# Audio_output_Codec.net
KiCad netlist of a schematic drawn in Altium Designer
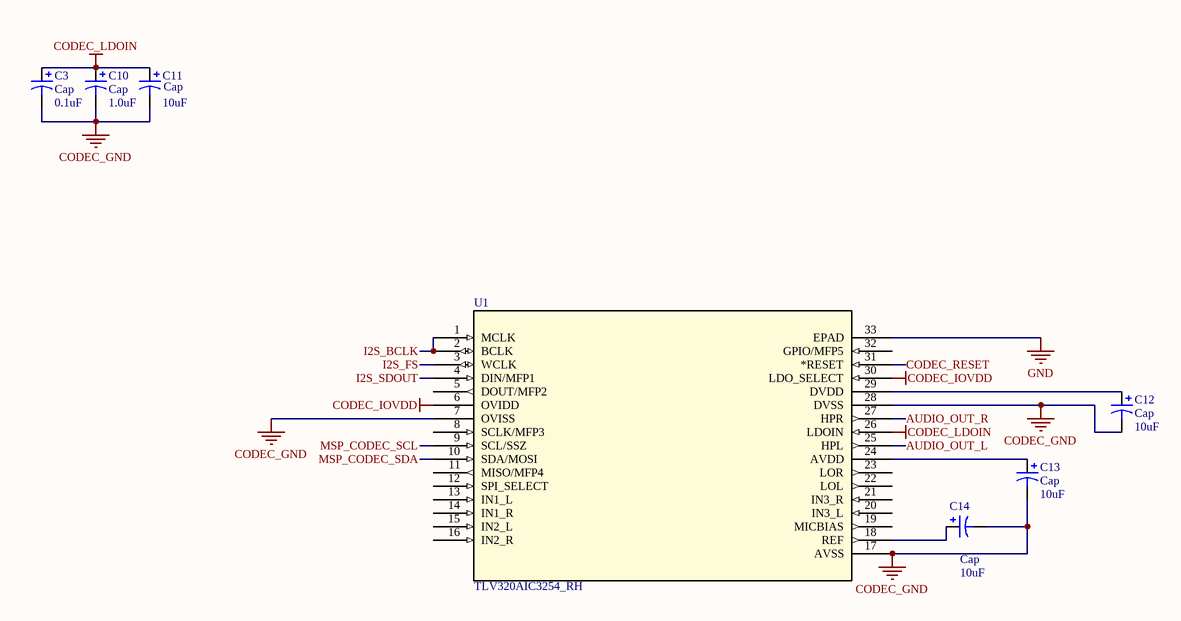
[diagram p0: Audio output Codec.SchDoc]

(export (version "E")
  (design (tool "Eeschema 10.0.6"))
  (components
    (comp (ref "C3")
      (value "Cap")
      (footprint "C0805")
      (description "Polarized Capacitor (Surface Mount)")
      (fields (field (name "ALTIUM_VALUE") "0.1uF") (field (name "PUBLISHER") "Altium Limited"))
      (libsource (lib "Miscellaneous Devices") (part "Cap Pol3"))
    )
    (comp (ref "C10")
      (value "Cap")
      (footprint "C0805")
      (description "Polarized Capacitor (Surface Mount)")
      (fields (field (name "ALTIUM_VALUE") "1.0uF") (field (name "PUBLISHER") "Altium Limited"))
      (libsource (lib "Miscellaneous Devices") (part "Cap Pol3"))
    )
    (comp (ref "C11")
      (value "Cap")
      (footprint "C0805")
      (description "Polarized Capacitor (Surface Mount)")
      (fields (field (name "ALTIUM_VALUE") "10uF") (field (name "PUBLISHER") "Altium Limited"))
      (libsource (lib "Miscellaneous Devices") (part "Cap Pol3"))
    )
    (comp (ref "C12")
      (value "Cap")
      (footprint "C0805")
      (description "Polarized Capacitor (Surface Mount)")
      (fields (field (name "ALTIUM_VALUE") "10uF") (field (name "PUBLISHER") "Altium Limited"))
      (libsource (lib "Miscellaneous Devices") (part "Cap Pol3"))
    )
    (comp (ref "C13")
      (value "Cap")
      (footprint "C0805")
      (description "Polarized Capacitor (Surface Mount)")
      (fields (field (name "ALTIUM_VALUE") "10uF") (field (name "PUBLISHER") "Altium Limited"))
      (libsource (lib "Miscellaneous Devices") (part "Cap Pol3"))
    )
    (comp (ref "C14")
      (value "Cap")
      (footprint "C0805")
      (description "Polarized Capacitor (Surface Mount)")
      (fields (field (name "ALTIUM_VALUE") "10uF") (field (name "PUBLISHER") "Altium Limited"))
      (libsource (lib "Miscellaneous Devices") (part "Cap Pol3"))
    )
    (comp (ref "U1")
      (value "TLV320AIC3254_RH")
      (footprint "RHB32_3P45X3P45")
      (description "Imported")
      (fields
        (field (name "MANUFACTURER_PART_NUMBER") "tlv320aic3254_rhb_32")
        (field (name "GENERIC_PART_NUMBER") "TLV320AIC3254")
      )
      (libsource (lib "Gator_Stream") (part "TLV320AIC3254_RH"))
    )
  )
  (nets
    (net (code "1") (name "/AUDIO_OUT_L") (class "Default")
      (node (ref "U1") (pin "25") (pinfunction "HPL_25") (pintype "output"))
    )
    (net (code "2") (name "/AUDIO_OUT_R") (class "Default")
      (node (ref "U1") (pin "27") (pinfunction "HPR_27") (pintype "output"))
    )
    (net (code "3") (name "/CODEC_RESET") (class "Default")
      (node (ref "U1") (pin "31") (pinfunction "*RESET_31") (pintype "input"))
    )
    (net (code "4") (name "/I2S_BCLK") (class "Default")
      (node (ref "U1") (pin "1") (pinfunction "MCLK_1") (pintype "input"))
      (node (ref "U1") (pin "2") (pinfunction "BCLK_2") (pintype "bidirectional"))
    )
    (net (code "5") (name "/I2S_FS") (class "Default")
      (node (ref "U1") (pin "3") (pinfunction "WCLK_3") (pintype "bidirectional"))
    )
    (net (code "6") (name "/I2S_SDOUT") (class "Default")
      (node (ref "U1") (pin "4") (pinfunction "DIN/MFP1_4") (pintype "input"))
    )
    (net (code "7") (name "/MSP_CODEC_SCL") (class "Default")
      (node (ref "U1") (pin "9") (pinfunction "SCL/SSZ_9") (pintype "input"))
    )
    (net (code "8") (name "/MSP_CODEC_SDA") (class "Default")
      (node (ref "U1") (pin "10") (pinfunction "SDA/MOSI_10") (pintype "input"))
    )
    (net (code "9") (name "CODEC_GND") (class "Default")
      (node (ref "C10") (pin "2") (pinfunction "2_2") (pintype "passive"))
      (node (ref "C11") (pin "2") (pinfunction "2_2") (pintype "passive"))
      (node (ref "C12") (pin "2") (pinfunction "2_2") (pintype "passive"))
      (node (ref "C13") (pin "2") (pinfunction "2_2") (pintype "passive"))
      (node (ref "C14") (pin "2") (pinfunction "2_2") (pintype "passive"))
      (node (ref "C3") (pin "2") (pinfunction "2_2") (pintype "passive"))
      (node (ref "U1") (pin "17") (pinfunction "AVSS_17") (pintype "power_in"))
      (node (ref "U1") (pin "28") (pinfunction "DVSS_28") (pintype "power_in"))
      (node (ref "U1") (pin "7") (pinfunction "OVISS_7") (pintype "power_in"))
    )
    (net (code "10") (name "CODEC_IOVDD") (class "Default")
      (node (ref "U1") (pin "30") (pinfunction "LDO_SELECT_30") (pintype "input"))
      (node (ref "U1") (pin "6") (pinfunction "OVIDD_6") (pintype "power_in"))
    )
    (net (code "11") (name "CODEC_LDOIN") (class "Default")
      (node (ref "C10") (pin "1") (pinfunction "1_1") (pintype "passive"))
      (node (ref "C11") (pin "1") (pinfunction "1_1") (pintype "passive"))
      (node (ref "C3") (pin "1") (pinfunction "1_1") (pintype "passive"))
      (node (ref "U1") (pin "26") (pinfunction "LDOIN_26") (pintype "input"))
    )
    (net (code "12") (name "GND") (class "Default")
      (node (ref "U1") (pin "33") (pinfunction "EPAD_33") (pintype "passive"))
    )
    (net (code "13") (name "Net-(U1-AVDD)") (class "Default")
      (node (ref "C13") (pin "1") (pinfunction "1_1") (pintype "passive"))
      (node (ref "U1") (pin "24") (pinfunction "AVDD_24") (pintype "power_in"))
    )
    (net (code "14") (name "Net-(U1-DVDD)") (class "Default")
      (node (ref "C12") (pin "1") (pinfunction "1_1") (pintype "passive"))
      (node (ref "U1") (pin "29") (pinfunction "DVDD_29") (pintype "power_in"))
    )
    (net (code "15") (name "Net-(U1-REF)") (class "Default")
      (node (ref "C14") (pin "1") (pinfunction "1_1") (pintype "passive"))
      (node (ref "U1") (pin "18") (pinfunction "REF_18") (pintype "output"))
    )
    (net (code "16") (name "unconnected-(U1-DOUT{slash}MFP2-Pad5)") (class "Default")
      (node (ref "U1") (pin "5") (pinfunction "DOUT/MFP2_5") (pintype "output"))
    )
    (net (code "17") (name "unconnected-(U1-GPIO{slash}MFP5-Pad32)") (class "Default")
      (node (ref "U1") (pin "32") (pinfunction "GPIO/MFP5_32") (pintype "input"))
    )
    (net (code "18") (name "unconnected-(U1-IN1_L-Pad13)") (class "Default")
      (node (ref "U1") (pin "13") (pinfunction "IN1_L_13") (pintype "input"))
    )
    (net (code "19") (name "unconnected-(U1-IN1_R-Pad14)") (class "Default")
      (node (ref "U1") (pin "14") (pinfunction "IN1_R_14") (pintype "input"))
    )
    (net (code "20") (name "unconnected-(U1-IN2_L-Pad15)") (class "Default")
      (node (ref "U1") (pin "15") (pinfunction "IN2_L_15") (pintype "input"))
    )
    (net (code "21") (name "unconnected-(U1-IN2_R-Pad16)") (class "Default")
      (node (ref "U1") (pin "16") (pinfunction "IN2_R_16") (pintype "input"))
    )
    (net (code "22") (name "unconnected-(U1-IN3_L-Pad20)") (class "Default")
      (node (ref "U1") (pin "20") (pinfunction "IN3_L_20") (pintype "input"))
    )
    (net (code "23") (name "unconnected-(U1-IN3_R-Pad21)") (class "Default")
      (node (ref "U1") (pin "21") (pinfunction "IN3_R_21") (pintype "input"))
    )
    (net (code "24") (name "unconnected-(U1-LOL-Pad22)") (class "Default")
      (node (ref "U1") (pin "22") (pinfunction "LOL_22") (pintype "output"))
    )
    (net (code "25") (name "unconnected-(U1-LOR-Pad23)") (class "Default")
      (node (ref "U1") (pin "23") (pinfunction "LOR_23") (pintype "output"))
    )
    (net (code "26") (name "unconnected-(U1-MICBIAS-Pad19)") (class "Default")
      (node (ref "U1") (pin "19") (pinfunction "MICBIAS_19") (pintype "output"))
    )
    (net (code "27") (name "unconnected-(U1-MISO{slash}MFP4-Pad11)") (class "Default")
      (node (ref "U1") (pin "11") (pinfunction "MISO/MFP4_11") (pintype "output"))
    )
    (net (code "28") (name "unconnected-(U1-SCLK{slash}MFP3-Pad8)") (class "Default")
      (node (ref "U1") (pin "8") (pinfunction "SCLK/MFP3_8") (pintype "input"))
    )
    (net (code "29") (name "unconnected-(U1-SPI_SELECT-Pad12)") (class "Default")
      (node (ref "U1") (pin "12") (pinfunction "SPI_SELECT_12") (pintype "input"))
    )
  )
)
